# 05_RFID.net
KiCad netlist of a schematic drawn in Altium Designer
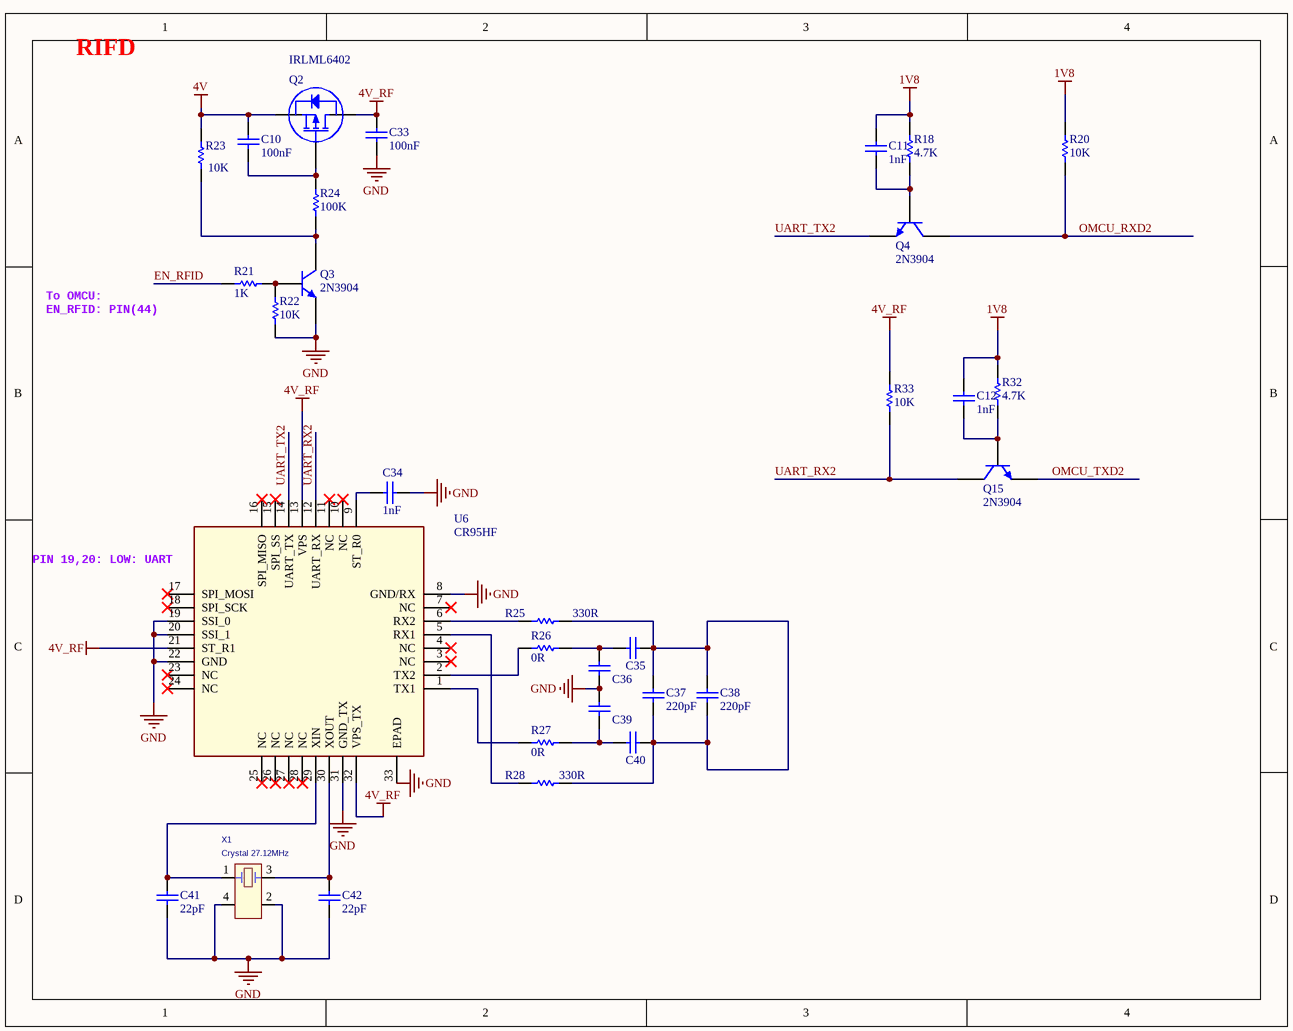
[diagram p0: 05 RFID.SchDoc]

(export (version "E")
  (design (tool "Eeschema 10.0.6"))
  (components
    (comp (ref "C10")
      (value "100nF")
      (footprint "0603 - C")
      (description "CAP CER 100nF 50V C0G/NP0 0603")
      (fields (field (name "MPN") "CL10C104JB8NNNC") (field (name "MFR") "SAMSUNG"))
      (libsource (lib "Library_Chip") (part "Cap 0603 100nF"))
    )
    (comp (ref "C11")
      (value "1nF")
      (footprint "0603 - C")
      (description "CAP CER 1000PF 50V C0G/NP0 0603")
      (fields (field (name "MPN") "CL10C102JB8NNNC") (field (name "MFR") "SAMSUNG"))
      (libsource (lib "Library_Chip") (part "Cap 0603 1nF"))
    )
    (comp (ref "C12")
      (value "1nF")
      (footprint "0603 - C")
      (description "CAP CER 1000PF 50V C0G/NP0 0603")
      (fields (field (name "MPN") "CL10C102JB8NNNC") (field (name "MFR") "SAMSUNG"))
      (libsource (lib "Library_Chip") (part "Cap 0603 1nF"))
    )
    (comp (ref "C33")
      (value "100nF")
      (footprint "0603 - C")
      (description "CAP CER 100nF 50V C0G/NP0 0603")
      (fields (field (name "MPN") "CL10C104JB8NNNC") (field (name "MFR") "SAMSUNG"))
      (libsource (lib "Library_Chip") (part "Cap 0603 100nF"))
    )
    (comp (ref "C34")
      (value "1nF")
      (footprint "0603 - C")
      (description "CAP CER 1000PF 50V C0G/NP0 0603")
      (fields (field (name "MPN") "CL10C102JB8NNNC") (field (name "MFR") "SAMSUNG"))
      (libsource (lib "Library_Chip") (part "Cap 0603 1nF"))
    )
    (comp (ref "C35")
      (value "150pF")
      (footprint "0603 - C")
      (description "CAP CER 150PF 50V C0G/NP0 0603")
      (fields (field (name "MPN") "CL10C151JB8NNNC") (field (name "MFR") "SAMSUNG"))
      (libsource (lib "Library_Chip") (part "Cap 0603 150pF"))
    )
    (comp (ref "C36")
      (value "150pF")
      (footprint "0603 - C")
      (description "CAP CER 150PF 50V C0G/NP0 0603")
      (fields (field (name "MPN") "CL10C151JB8NNNC") (field (name "MFR") "SAMSUNG"))
      (libsource (lib "Library_Chip") (part "Cap 0603 150pF"))
    )
    (comp (ref "C37")
      (value "220pF")
      (footprint "0603 - C")
      (description "CAP CER 220PF 50V C0G/NP0 0603")
      (fields (field (name "MPN") "CL10C221JB8NNNC") (field (name "MFR") "SAMSUNG"))
      (libsource (lib "Library_Chip") (part "Cap 0603 220pF"))
    )
    (comp (ref "C38")
      (value "220pF")
      (footprint "0603 - C")
      (description "CAP CER 220PF 50V C0G/NP0 0603")
      (fields (field (name "MPN") "CL10C221JB8NNNC") (field (name "MFR") "SAMSUNG"))
      (libsource (lib "Library_Chip") (part "Cap 0603 220pF"))
    )
    (comp (ref "C39")
      (value "150pF")
      (footprint "0603 - C")
      (description "CAP CER 150PF 50V C0G/NP0 0603")
      (fields (field (name "MPN") "CL10C151JB8NNNC") (field (name "MFR") "SAMSUNG"))
      (libsource (lib "Library_Chip") (part "Cap 0603 150pF"))
    )
    (comp (ref "C40")
      (value "150pF")
      (footprint "0603 - C")
      (description "CAP CER 150PF 50V C0G/NP0 0603")
      (fields (field (name "MPN") "CL10C151JB8NNNC") (field (name "MFR") "SAMSUNG"))
      (libsource (lib "Library_Chip") (part "Cap 0603 150pF"))
    )
    (comp (ref "C41")
      (value "22pF")
      (footprint "0603 - C")
      (description "CAP CER 22PF 50V C0G/NP0 0603")
      (fields (field (name "MPN") "CL10C220JB8NNNC") (field (name "MFR") "SAMSUNG"))
      (libsource (lib "Library_Chip") (part "Cap 0603 22pF"))
    )
    (comp (ref "C42")
      (value "22pF")
      (footprint "0603 - C")
      (description "CAP CER 22PF 50V C0G/NP0 0603")
      (fields (field (name "MPN") "CL10C220JB8NNNC") (field (name "MFR") "SAMSUNG"))
      (libsource (lib "Library_Chip") (part "Cap 0603 22pF"))
    )
    (comp (ref "Q2")
      (value "IRLML6402")
      (footprint "SOT23B")
      (description "MOSFET P-CH 30V 3.6A SOT-23-3")
      (fields (field (name "MPN") "IRLML6402TRPBF") (field (name "MFR") "Infineon Technologies"))
      (libsource (lib "Library") (part "IRLML6402TRPBF"))
    )
    (comp (ref "Q3")
      (value "2N3904")
      (footprint "SOT23B")
      (description "TRANS NPN 40V 0.2A SOT-23")
      (fields (field (name "MPN") "MMBT3904") (field (name "MFR") "Fairchild"))
      (libsource (lib "Library_Chip") (part "Transistor 2N3904"))
    )
    (comp (ref "Q4")
      (value "2N3904")
      (footprint "SOT23B")
      (description "TRANS NPN 40V 0.2A SOT-23")
      (fields (field (name "MPN") "MMBT3904") (field (name "MFR") "Fairchild"))
      (libsource (lib "Library_Chip") (part "Transistor 2N3904"))
    )
    (comp (ref "Q15")
      (value "2N3904")
      (footprint "SOT23B")
      (description "TRANS NPN 40V 0.2A SOT-23")
      (fields (field (name "MPN") "MMBT3904") (field (name "MFR") "Fairchild"))
      (libsource (lib "Library_Chip") (part "Transistor 2N3904"))
    )
    (comp (ref "R18")
      (value "4.7K")
      (footprint "0603 - R")
      (description "RES SMD 4.7K OHM 1% 1/10W 0603")
      (fields (field (name "MFR") "Yageo") (field (name "MPN") "RC0603FR-074K7L"))
      (libsource (lib "Library_Chip") (part "Res 0603 4.7K"))
    )
    (comp (ref "R20")
      (value "10K")
      (footprint "0603 - R")
      (description "RES SMD 10K OHM 1% 1/10W 0603")
      (fields (field (name "MFR") "Yageo") (field (name "MPN") "RC0603FR-0710KL"))
      (libsource (lib "Library_Chip") (part "Res 0603 10K"))
    )
    (comp (ref "R21")
      (value "1K")
      (footprint "0603 - R")
      (description "RES SMD 1K OHM 1% 1/10W 0603")
      (fields (field (name "MFR") "Yageo") (field (name "MPN") "RC0603FR-071KL"))
      (libsource (lib "Library_Chip") (part "Res 0603 1K"))
    )
    (comp (ref "R22")
      (value "10K")
      (footprint "0603 - R")
      (description "RES SMD 10K OHM 1% 1/10W 0603")
      (fields (field (name "MFR") "Yageo") (field (name "MPN") "RC0603FR-0710KL"))
      (libsource (lib "Library_Chip") (part "Res 0603 10K"))
    )
    (comp (ref "R23")
      (value "10K")
      (footprint "0603 - R")
      (description "RES SMD 10K OHM 1% 1/10W 0603")
      (fields (field (name "MFR") "Yageo") (field (name "MPN") "RC0603FR-0710KL"))
      (libsource (lib "Library_Chip") (part "Res 0603 10K"))
    )
    (comp (ref "R24")
      (value "100K")
      (footprint "0603 - R")
      (description "RES SMD 100K OHM 1% 1/10W 0603")
      (fields (field (name "MFR") "Yageo") (field (name "MPN") "RC0603FR-07100KL"))
      (libsource (lib "Library_Chip") (part "Res 0603 100K"))
    )
    (comp (ref "R25")
      (value "330R")
      (footprint "0603 - R")
      (description "RES SMD 330OHM 1% 1/10W 0603")
      (fields (field (name "MFR") "Yageo") (field (name "MPN") "RC0603FR-07330RL"))
      (libsource (lib "Library_Chip") (part "Res 0603 330R"))
    )
    (comp (ref "R26")
      (value "0R")
      (footprint "0603 - R")
      (description "RES SMD 0 OHM JUMPER 1/10W 0603")
      (fields (field (name "MFR") "Yageo") (field (name "MPN") "RC0603FR-070RL"))
      (libsource (lib "Library_Chip") (part "Res 0603 0R"))
    )
    (comp (ref "R27")
      (value "0R")
      (footprint "0603 - R")
      (description "RES SMD 0 OHM JUMPER 1/10W 0603")
      (fields (field (name "MFR") "Yageo") (field (name "MPN") "RC0603FR-070RL"))
      (libsource (lib "Library_Chip") (part "Res 0603 0R"))
    )
    (comp (ref "R28")
      (value "330R")
      (footprint "0603 - R")
      (description "RES SMD 330OHM 1% 1/10W 0603")
      (fields (field (name "MFR") "Yageo") (field (name "MPN") "RC0603FR-07330RL"))
      (libsource (lib "Library_Chip") (part "Res 0603 330R"))
    )
    (comp (ref "R32")
      (value "4.7K")
      (footprint "0603 - R")
      (description "RES SMD 4.7K OHM 1% 1/10W 0603")
      (fields (field (name "MFR") "Yageo") (field (name "MPN") "RC0603FR-074K7L"))
      (libsource (lib "Library_Chip") (part "Res 0603 4.7K"))
    )
    (comp (ref "R33")
      (value "10K")
      (footprint "0603 - R")
      (description "RES SMD 10K OHM 1% 1/10W 0603")
      (fields (field (name "MFR") "Yageo") (field (name "MPN") "RC0603FR-0710KL"))
      (libsource (lib "Library_Chip") (part "Res 0603 10K"))
    )
    (comp (ref "U6")
      (value "CR95HF")
      (footprint "32-VFQFN")
      (description "IC RFID RDR/TRN 13.56MZ 32VFQFPN")
      (fields (field (name "MPN") "CR95HF-VMD5T") (field (name "MFR") "ST"))
      (libsource (lib "Library_IC") (part "CR95HF"))
    )
    (comp (ref "X1")
      (value "Crystal 27.12MHz")
      (footprint "Crystal 2016")
      (description "CRYSTAL 27.12MHz RoHS")
      (fields (field (name "MPN") "XRCGB27M120F3M00R0") (field (name "MFR") "Murata"))
      (libsource (lib "Library_Chip") (part "XTAL-XRCBG27M"))
    )
  )
  (nets
    (net (code "1") (name "/EN_RFID") (class "Default")
      (node (ref "R21") (pin "1") (pinfunction "1_1") (pintype "passive"))
    )
    (net (code "2") (name "/OMCU_RXD2") (class "Default")
      (node (ref "Q4") (pin "3") (pinfunction "C_3") (pintype "passive"))
      (node (ref "R20") (pin "1") (pinfunction "1_1") (pintype "passive"))
    )
    (net (code "3") (name "/OMCU_TXD2") (class "Default")
      (node (ref "Q15") (pin "2") (pinfunction "E_2") (pintype "passive"))
    )
    (net (code "4") (name "/UART_RX2") (class "Default")
      (node (ref "Q15") (pin "3") (pinfunction "C_3") (pintype "passive"))
      (node (ref "R33") (pin "1") (pinfunction "1_1") (pintype "passive"))
      (node (ref "U6") (pin "12") (pinfunction "UART_RX_12") (pintype "passive"))
    )
    (net (code "5") (name "/UART_TX2") (class "Default")
      (node (ref "Q4") (pin "2") (pinfunction "E_2") (pintype "passive"))
      (node (ref "U6") (pin "14") (pinfunction "UART_TX_14") (pintype "passive"))
    )
    (net (code "6") (name "1V8") (class "Default")
      (node (ref "C11") (pin "2") (pinfunction "2_2") (pintype "passive"))
      (node (ref "C12") (pin "2") (pinfunction "2_2") (pintype "passive"))
      (node (ref "R18") (pin "2") (pinfunction "2_2") (pintype "passive"))
      (node (ref "R20") (pin "2") (pinfunction "2_2") (pintype "passive"))
      (node (ref "R32") (pin "2") (pinfunction "2_2") (pintype "passive"))
    )
    (net (code "7") (name "4V") (class "Default")
      (node (ref "C10") (pin "2") (pinfunction "2_2") (pintype "passive"))
      (node (ref "Q2") (pin "2") (pinfunction "S_2") (pintype "passive"))
      (node (ref "R23") (pin "2") (pinfunction "2_2") (pintype "passive"))
    )
    (net (code "8") (name "4V_RF") (class "Default")
      (node (ref "C33") (pin "2") (pinfunction "2_2") (pintype "passive"))
      (node (ref "Q2") (pin "3") (pinfunction "D_3") (pintype "passive"))
      (node (ref "R33") (pin "2") (pinfunction "2_2") (pintype "passive"))
      (node (ref "U6") (pin "13") (pinfunction "VPS_13") (pintype "passive"))
      (node (ref "U6") (pin "21") (pinfunction "ST_R1_21") (pintype "passive"))
      (node (ref "U6") (pin "32") (pinfunction "VPS_TX_32") (pintype "passive"))
    )
    (net (code "9") (name "GND") (class "Default")
      (node (ref "C33") (pin "1") (pinfunction "1_1") (pintype "passive"))
      (node (ref "C34") (pin "2") (pinfunction "2_2") (pintype "passive"))
      (node (ref "C36") (pin "1") (pinfunction "1_1") (pintype "passive"))
      (node (ref "C39") (pin "2") (pinfunction "2_2") (pintype "passive"))
      (node (ref "C41") (pin "1") (pinfunction "1_1") (pintype "passive"))
      (node (ref "C42") (pin "1") (pinfunction "1_1") (pintype "passive"))
      (node (ref "Q3") (pin "2") (pinfunction "E_2") (pintype "passive"))
      (node (ref "R22") (pin "1") (pinfunction "1_1") (pintype "passive"))
      (node (ref "U6") (pin "19") (pinfunction "SSI_0_19") (pintype "passive"))
      (node (ref "U6") (pin "20") (pinfunction "SSI_1_20") (pintype "passive"))
      (node (ref "U6") (pin "22") (pinfunction "GND_22") (pintype "passive"))
      (node (ref "U6") (pin "31") (pinfunction "GND_TX_31") (pintype "passive"))
      (node (ref "U6") (pin "33") (pinfunction "EPAD_33") (pintype "passive"))
      (node (ref "U6") (pin "8") (pinfunction "GND/RX_8") (pintype "passive"))
      (node (ref "X1") (pin "2") (pinfunction "GND_2") (pintype "power_in"))
      (node (ref "X1") (pin "4") (pinfunction "GND_4") (pintype "power_in"))
    )
    (net (code "10") (name "Net-(C35-Pad1)") (class "Default")
      (node (ref "C35") (pin "1") (pinfunction "1_1") (pintype "passive"))
      (node (ref "C36") (pin "2") (pinfunction "2_2") (pintype "passive"))
      (node (ref "R26") (pin "2") (pinfunction "2_2") (pintype "passive"))
    )
    (net (code "11") (name "Net-(C35-Pad2)") (class "Default")
      (node (ref "C35") (pin "2") (pinfunction "2_2") (pintype "passive"))
      (node (ref "C37") (pin "1") (pinfunction "1_1") (pintype "passive"))
      (node (ref "C37") (pin "2") (pinfunction "2_2") (pintype "passive"))
      (node (ref "C38") (pin "1") (pinfunction "1_1") (pintype "passive"))
      (node (ref "C38") (pin "2") (pinfunction "2_2") (pintype "passive"))
      (node (ref "C40") (pin "2") (pinfunction "2_2") (pintype "passive"))
      (node (ref "R25") (pin "2") (pinfunction "2_2") (pintype "passive"))
      (node (ref "R28") (pin "2") (pinfunction "2_2") (pintype "passive"))
    )
    (net (code "12") (name "Net-(C39-Pad1)") (class "Default")
      (node (ref "C39") (pin "1") (pinfunction "1_1") (pintype "passive"))
      (node (ref "C40") (pin "1") (pinfunction "1_1") (pintype "passive"))
      (node (ref "R27") (pin "2") (pinfunction "2_2") (pintype "passive"))
    )
    (net (code "13") (name "Net-(Q2-G)") (class "Default")
      (node (ref "C10") (pin "1") (pinfunction "1_1") (pintype "passive"))
      (node (ref "Q2") (pin "1") (pinfunction "G_1") (pintype "passive"))
      (node (ref "R24") (pin "2") (pinfunction "2_2") (pintype "passive"))
    )
    (net (code "14") (name "Net-(Q3-B)") (class "Default")
      (node (ref "Q3") (pin "1") (pinfunction "B_1") (pintype "passive"))
      (node (ref "R21") (pin "2") (pinfunction "2_2") (pintype "passive"))
      (node (ref "R22") (pin "2") (pinfunction "2_2") (pintype "passive"))
    )
    (net (code "15") (name "Net-(Q3-C)") (class "Default")
      (node (ref "Q3") (pin "3") (pinfunction "C_3") (pintype "passive"))
      (node (ref "R23") (pin "1") (pinfunction "1_1") (pintype "passive"))
      (node (ref "R24") (pin "1") (pinfunction "1_1") (pintype "passive"))
    )
    (net (code "16") (name "Net-(Q4-B)") (class "Default")
      (node (ref "C11") (pin "1") (pinfunction "1_1") (pintype "passive"))
      (node (ref "Q4") (pin "1") (pinfunction "B_1") (pintype "passive"))
      (node (ref "R18") (pin "1") (pinfunction "1_1") (pintype "passive"))
    )
    (net (code "17") (name "Net-(Q15-B)") (class "Default")
      (node (ref "C12") (pin "1") (pinfunction "1_1") (pintype "passive"))
      (node (ref "Q15") (pin "1") (pinfunction "B_1") (pintype "passive"))
      (node (ref "R32") (pin "1") (pinfunction "1_1") (pintype "passive"))
    )
    (net (code "18") (name "Net-(U6-RX1)") (class "Default")
      (node (ref "R28") (pin "1") (pinfunction "1_1") (pintype "passive"))
      (node (ref "U6") (pin "5") (pinfunction "RX1_5") (pintype "passive"))
    )
    (net (code "19") (name "Net-(U6-RX2)") (class "Default")
      (node (ref "R25") (pin "1") (pinfunction "1_1") (pintype "passive"))
      (node (ref "U6") (pin "6") (pinfunction "RX2_6") (pintype "passive"))
    )
    (net (code "20") (name "Net-(U6-ST_R0)") (class "Default")
      (node (ref "C34") (pin "1") (pinfunction "1_1") (pintype "passive"))
      (node (ref "U6") (pin "9") (pinfunction "ST_R0_9") (pintype "passive"))
    )
    (net (code "21") (name "Net-(U6-TX1)") (class "Default")
      (node (ref "R27") (pin "1") (pinfunction "1_1") (pintype "passive"))
      (node (ref "U6") (pin "1") (pinfunction "TX1_1") (pintype "passive"))
    )
    (net (code "22") (name "Net-(U6-TX2)") (class "Default")
      (node (ref "R26") (pin "1") (pinfunction "1_1") (pintype "passive"))
      (node (ref "U6") (pin "2") (pinfunction "TX2_2") (pintype "passive"))
    )
    (net (code "23") (name "Net-(U6-XIN)") (class "Default")
      (node (ref "C41") (pin "2") (pinfunction "2_2") (pintype "passive"))
      (node (ref "U6") (pin "29") (pinfunction "XIN_29") (pintype "passive"))
      (node (ref "X1") (pin "1") (pinfunction "OSC1_1") (pintype "passive"))
    )
    (net (code "24") (name "Net-(U6-XOUT)") (class "Default")
      (node (ref "C42") (pin "2") (pinfunction "2_2") (pintype "passive"))
      (node (ref "U6") (pin "30") (pinfunction "XOUT_30") (pintype "passive"))
      (node (ref "X1") (pin "3") (pinfunction "OSC2_3") (pintype "passive"))
    )
    (net (code "25") (name "unconnected-(U6-NC-Pad3)") (class "Default")
      (node (ref "U6") (pin "3") (pinfunction "NC_3") (pintype "passive+no_connect"))
    )
    (net (code "26") (name "unconnected-(U6-NC-Pad4)") (class "Default")
      (node (ref "U6") (pin "4") (pinfunction "NC_4") (pintype "passive+no_connect"))
    )
    (net (code "27") (name "unconnected-(U6-NC-Pad7)") (class "Default")
      (node (ref "U6") (pin "7") (pinfunction "NC_7") (pintype "passive+no_connect"))
    )
    (net (code "28") (name "unconnected-(U6-NC-Pad10)") (class "Default")
      (node (ref "U6") (pin "10") (pinfunction "NC_10") (pintype "passive+no_connect"))
    )
    (net (code "29") (name "unconnected-(U6-NC-Pad11)") (class "Default")
      (node (ref "U6") (pin "11") (pinfunction "NC_11") (pintype "passive+no_connect"))
    )
    (net (code "30") (name "unconnected-(U6-NC-Pad23)") (class "Default")
      (node (ref "U6") (pin "23") (pinfunction "NC_23") (pintype "passive+no_connect"))
    )
    (net (code "31") (name "unconnected-(U6-NC-Pad24)") (class "Default")
      (node (ref "U6") (pin "24") (pinfunction "NC_24") (pintype "passive+no_connect"))
    )
    (net (code "32") (name "unconnected-(U6-NC-Pad25)") (class "Default")
      (node (ref "U6") (pin "25") (pinfunction "NC_25") (pintype "passive+no_connect"))
    )
    (net (code "33") (name "unconnected-(U6-NC-Pad26)") (class "Default")
      (node (ref "U6") (pin "26") (pinfunction "NC_26") (pintype "passive+no_connect"))
    )
    (net (code "34") (name "unconnected-(U6-NC-Pad27)") (class "Default")
      (node (ref "U6") (pin "27") (pinfunction "NC_27") (pintype "passive+no_connect"))
    )
    (net (code "35") (name "unconnected-(U6-NC-Pad28)") (class "Default")
      (node (ref "U6") (pin "28") (pinfunction "NC_28") (pintype "passive+no_connect"))
    )
    (net (code "36") (name "unconnected-(U6-SPI_MISO-Pad16)") (class "Default")
      (node (ref "U6") (pin "16") (pinfunction "SPI_MISO_16") (pintype "passive+no_connect"))
    )
    (net (code "37") (name "unconnected-(U6-SPI_MOSI-Pad17)") (class "Default")
      (node (ref "U6") (pin "17") (pinfunction "SPI_MOSI_17") (pintype "passive+no_connect"))
    )
    (net (code "38") (name "unconnected-(U6-SPI_SCK-Pad18)") (class "Default")
      (node (ref "U6") (pin "18") (pinfunction "SPI_SCK_18") (pintype "passive+no_connect"))
    )
    (net (code "39") (name "unconnected-(U6-SPI_SS-Pad15)") (class "Default")
      (node (ref "U6") (pin "15") (pinfunction "SPI_SS_15") (pintype "passive+no_connect"))
    )
  )
)
